# BatteryModuleBoard.net
KiCad netlist of a schematic drawn in EAGLE
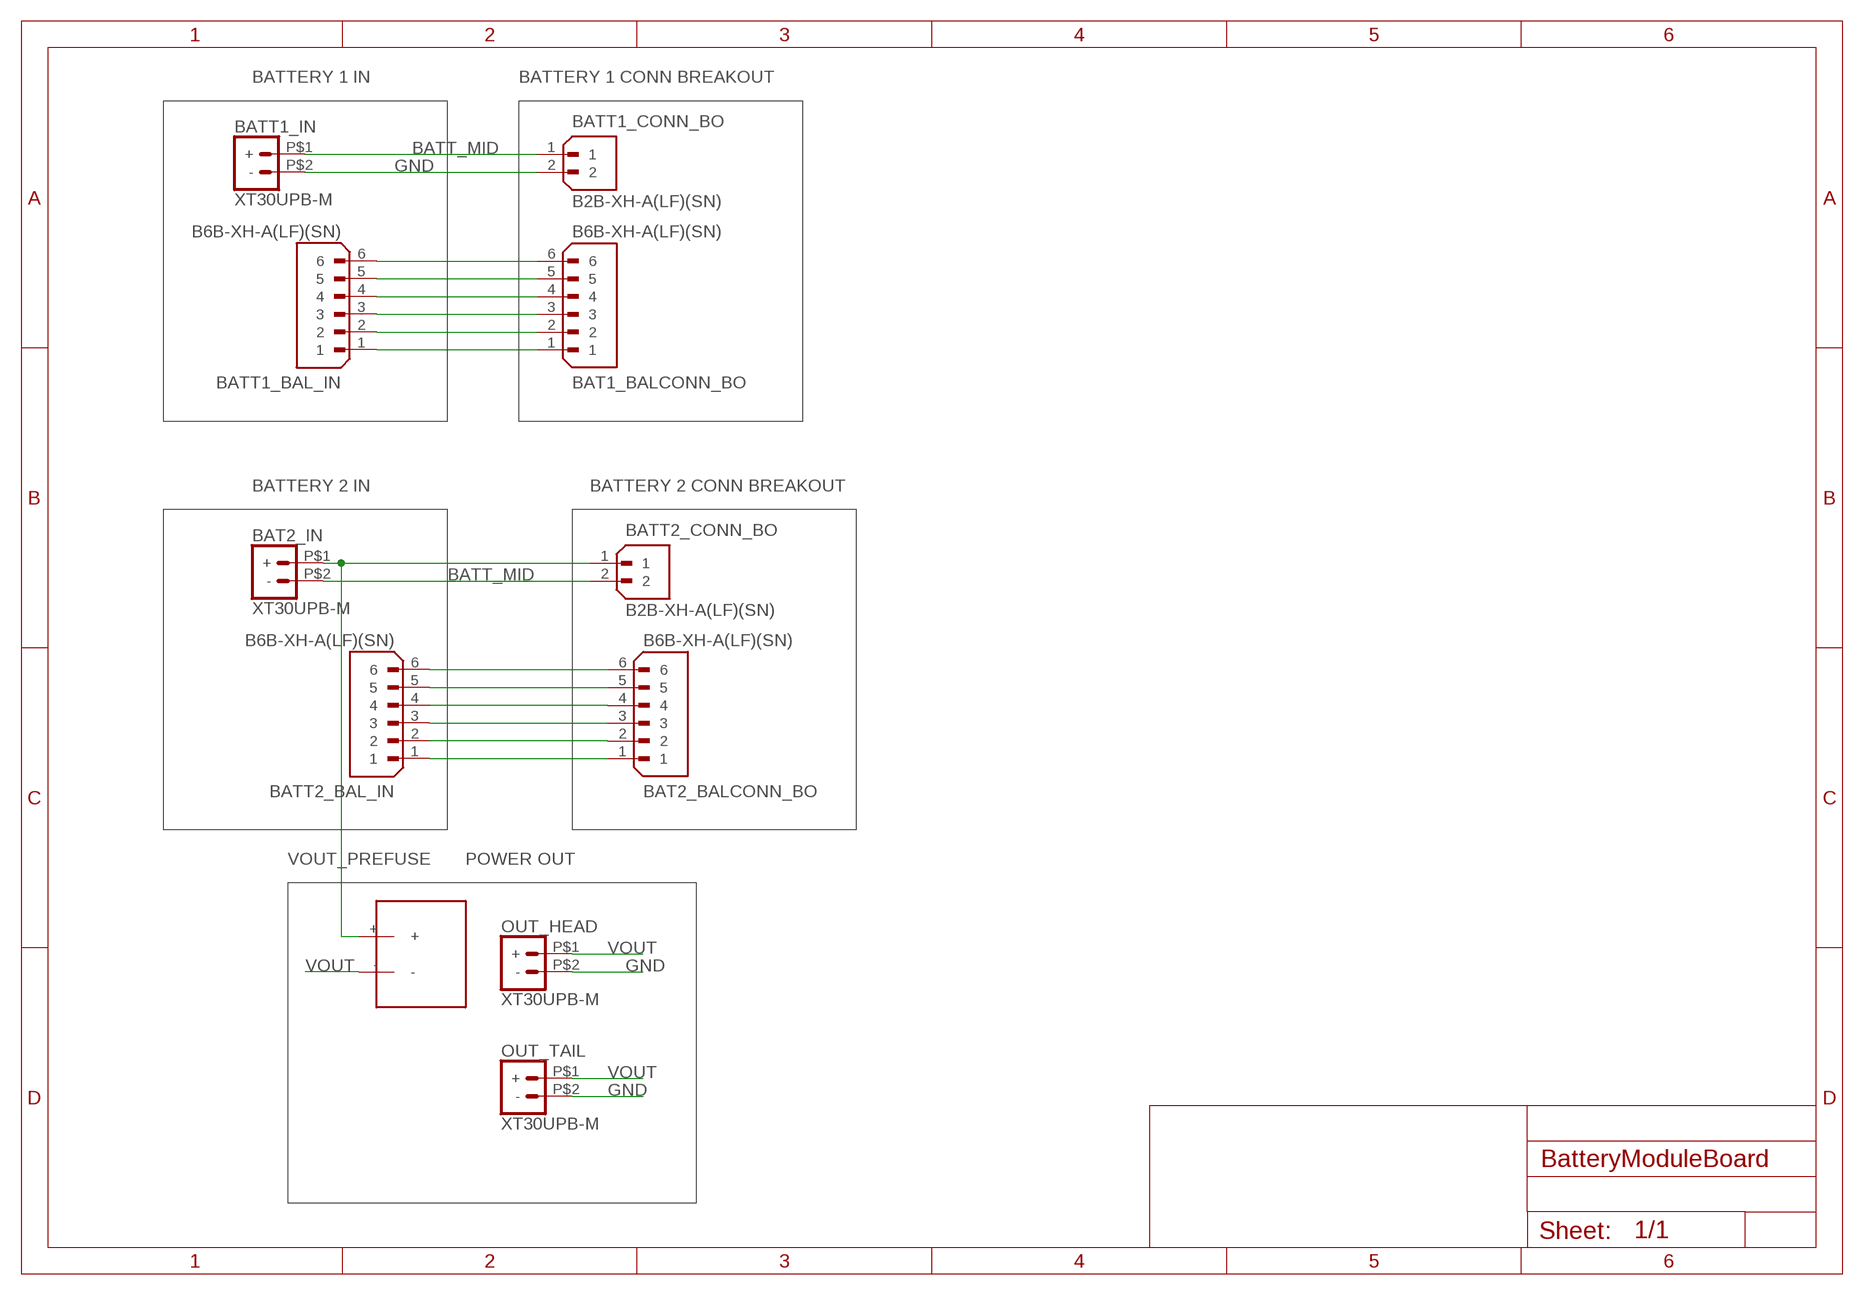
[diagram p0: schematic, sheet 1]

(export (version "E")
  (design (tool "Eeschema 10.0.6"))
  (components
    (comp (ref "BAT1_BALCONN_BO")
      (value "B6B-XH-A(LF)(SN)")
      (footprint "eagle-import:JST_B6B-XH-A(LF)(SN)")
      (fields (field (name "MF") "JST Sales"))
      (libsource (lib "eagle-import") (part "B6B-XH-A(LF)(SN)"))
    )
    (comp (ref "BAT2_BALCONN_BO")
      (value "B6B-XH-A(LF)(SN)")
      (footprint "eagle-import:JST_B6B-XH-A(LF)(SN)")
      (fields (field (name "MF") "JST Sales"))
      (libsource (lib "eagle-import") (part "B6B-XH-A(LF)(SN)"))
    )
    (comp (ref "BAT2_IN")
      (value "XT30UPB-M")
      (footprint "eagle-import:XT30UPB-M")
      (fields (field (name "MF") "amass"))
      (libsource (lib "eagle-import") (part "XT30UPB-M"))
    )
    (comp (ref "BATT1_BAL_IN")
      (value "B6B-XH-A(LF)(SN)")
      (footprint "eagle-import:JST_B6B-XH-A(LF)(SN)")
      (fields (field (name "MF") "JST Sales"))
      (libsource (lib "eagle-import") (part "B6B-XH-A(LF)(SN)"))
    )
    (comp (ref "BATT1_CONN_BO")
      (value "B2B-XH-A(LF)(SN)")
      (footprint "eagle-import:JST_B2B-XH-A(LF)(SN)")
      (fields (field (name "MF") "JST Sales America Inc."))
      (libsource (lib "eagle-import") (part "B2B-XH-A(LF)(SN)"))
    )
    (comp (ref "BATT1_IN")
      (value "XT30UPB-M")
      (footprint "eagle-import:XT30UPB-M")
      (fields (field (name "MF") "amass"))
      (libsource (lib "eagle-import") (part "XT30UPB-M"))
    )
    (comp (ref "BATT2_BAL_IN")
      (value "B6B-XH-A(LF)(SN)")
      (footprint "eagle-import:JST_B6B-XH-A(LF)(SN)")
      (fields (field (name "MF") "JST Sales"))
      (libsource (lib "eagle-import") (part "B6B-XH-A(LF)(SN)"))
    )
    (comp (ref "BATT2_CONN_BO")
      (value "B2B-XH-A(LF)(SN)")
      (footprint "eagle-import:JST_B2B-XH-A(LF)(SN)")
      (fields (field (name "MF") "JST Sales America Inc."))
      (libsource (lib "eagle-import") (part "B2B-XH-A(LF)(SN)"))
    )
    (comp (ref "FUSE")
      (value "SETSAFE_C1_FUSE")
      (footprint "eagle-import:SETSAFE_C1_FUSE")
      (libsource (lib "eagle-import") (part "SETSAFE_C1_FUSE"))
    )
    (comp (ref "OUT_HEAD")
      (value "XT30UPB-M")
      (footprint "eagle-import:XT30UPB-M")
      (fields (field (name "MF") "amass"))
      (libsource (lib "eagle-import") (part "XT30UPB-M"))
    )
    (comp (ref "OUT_TAIL")
      (value "XT30UPB-M")
      (footprint "eagle-import:XT30UPB-M")
      (fields (field (name "MF") "amass"))
      (libsource (lib "eagle-import") (part "XT30UPB-M"))
    )
  )
  (nets
    (net (code "1") (name "/BATT_MID") (class "Default")
      (node (ref "BAT2_IN") (pin "P$2") (pinfunction "-_P$2") (pintype "passive"))
      (node (ref "BATT1_CONN_BO") (pin "1") (pinfunction "1_1") (pintype "passive"))
      (node (ref "BATT1_IN") (pin "P$1") (pinfunction "+_P$1") (pintype "passive"))
      (node (ref "BATT2_CONN_BO") (pin "2") (pinfunction "2_2") (pintype "passive"))
    )
    (net (code "2") (name "/GND") (class "Default")
      (node (ref "BATT1_CONN_BO") (pin "2") (pinfunction "2_2") (pintype "passive"))
      (node (ref "BATT1_IN") (pin "P$2") (pinfunction "-_P$2") (pintype "passive"))
      (node (ref "OUT_HEAD") (pin "P$2") (pinfunction "-_P$2") (pintype "passive"))
      (node (ref "OUT_TAIL") (pin "P$2") (pinfunction "-_P$2") (pintype "passive"))
    )
    (net (code "3") (name "/VOUT") (class "Default")
      (node (ref "FUSE") (pin "-") (pinfunction "-_-") (pintype "bidirectional"))
      (node (ref "OUT_HEAD") (pin "P$1") (pinfunction "+_P$1") (pintype "passive"))
      (node (ref "OUT_TAIL") (pin "P$1") (pinfunction "+_P$1") (pintype "passive"))
    )
    (net (code "4") (name "/VOUT_PREFUSE") (class "Default")
      (node (ref "BAT2_IN") (pin "P$1") (pinfunction "+_P$1") (pintype "passive"))
      (node (ref "BATT2_CONN_BO") (pin "1") (pinfunction "1_1") (pintype "passive"))
      (node (ref "FUSE") (pin "+") (pinfunction "+_+") (pintype "bidirectional"))
    )
    (net (code "5") (name "Net-(BAT1_BALCONN_BO-Pad1)") (class "Default")
      (node (ref "BAT1_BALCONN_BO") (pin "1") (pinfunction "1_1") (pintype "passive"))
      (node (ref "BATT1_BAL_IN") (pin "1") (pinfunction "1_1") (pintype "passive"))
    )
    (net (code "6") (name "Net-(BAT1_BALCONN_BO-Pad2)") (class "Default")
      (node (ref "BAT1_BALCONN_BO") (pin "2") (pinfunction "2_2") (pintype "passive"))
      (node (ref "BATT1_BAL_IN") (pin "2") (pinfunction "2_2") (pintype "passive"))
    )
    (net (code "7") (name "Net-(BAT1_BALCONN_BO-Pad3)") (class "Default")
      (node (ref "BAT1_BALCONN_BO") (pin "3") (pinfunction "3_3") (pintype "passive"))
      (node (ref "BATT1_BAL_IN") (pin "3") (pinfunction "3_3") (pintype "passive"))
    )
    (net (code "8") (name "Net-(BAT1_BALCONN_BO-Pad4)") (class "Default")
      (node (ref "BAT1_BALCONN_BO") (pin "4") (pinfunction "4_4") (pintype "passive"))
      (node (ref "BATT1_BAL_IN") (pin "4") (pinfunction "4_4") (pintype "passive"))
    )
    (net (code "9") (name "Net-(BAT1_BALCONN_BO-Pad5)") (class "Default")
      (node (ref "BAT1_BALCONN_BO") (pin "5") (pinfunction "5_5") (pintype "passive"))
      (node (ref "BATT1_BAL_IN") (pin "5") (pinfunction "5_5") (pintype "passive"))
    )
    (net (code "10") (name "Net-(BAT1_BALCONN_BO-Pad6)") (class "Default")
      (node (ref "BAT1_BALCONN_BO") (pin "6") (pinfunction "6_6") (pintype "passive"))
      (node (ref "BATT1_BAL_IN") (pin "6") (pinfunction "6_6") (pintype "passive"))
    )
    (net (code "11") (name "Net-(BAT2_BALCONN_BO-Pad1)") (class "Default")
      (node (ref "BAT2_BALCONN_BO") (pin "1") (pinfunction "1_1") (pintype "passive"))
      (node (ref "BATT2_BAL_IN") (pin "1") (pinfunction "1_1") (pintype "passive"))
    )
    (net (code "12") (name "Net-(BAT2_BALCONN_BO-Pad2)") (class "Default")
      (node (ref "BAT2_BALCONN_BO") (pin "2") (pinfunction "2_2") (pintype "passive"))
      (node (ref "BATT2_BAL_IN") (pin "2") (pinfunction "2_2") (pintype "passive"))
    )
    (net (code "13") (name "Net-(BAT2_BALCONN_BO-Pad3)") (class "Default")
      (node (ref "BAT2_BALCONN_BO") (pin "3") (pinfunction "3_3") (pintype "passive"))
      (node (ref "BATT2_BAL_IN") (pin "3") (pinfunction "3_3") (pintype "passive"))
    )
    (net (code "14") (name "Net-(BAT2_BALCONN_BO-Pad4)") (class "Default")
      (node (ref "BAT2_BALCONN_BO") (pin "4") (pinfunction "4_4") (pintype "passive"))
      (node (ref "BATT2_BAL_IN") (pin "4") (pinfunction "4_4") (pintype "passive"))
    )
    (net (code "15") (name "Net-(BAT2_BALCONN_BO-Pad5)") (class "Default")
      (node (ref "BAT2_BALCONN_BO") (pin "5") (pinfunction "5_5") (pintype "passive"))
      (node (ref "BATT2_BAL_IN") (pin "5") (pinfunction "5_5") (pintype "passive"))
    )
    (net (code "16") (name "Net-(BAT2_BALCONN_BO-Pad6)") (class "Default")
      (node (ref "BAT2_BALCONN_BO") (pin "6") (pinfunction "6_6") (pintype "passive"))
      (node (ref "BATT2_BAL_IN") (pin "6") (pinfunction "6_6") (pintype "passive"))
    )
  )
)
